# FRDM-MCXA153__Shield_Template.net
KiCad netlist of a schematic drawn in Altium Designer
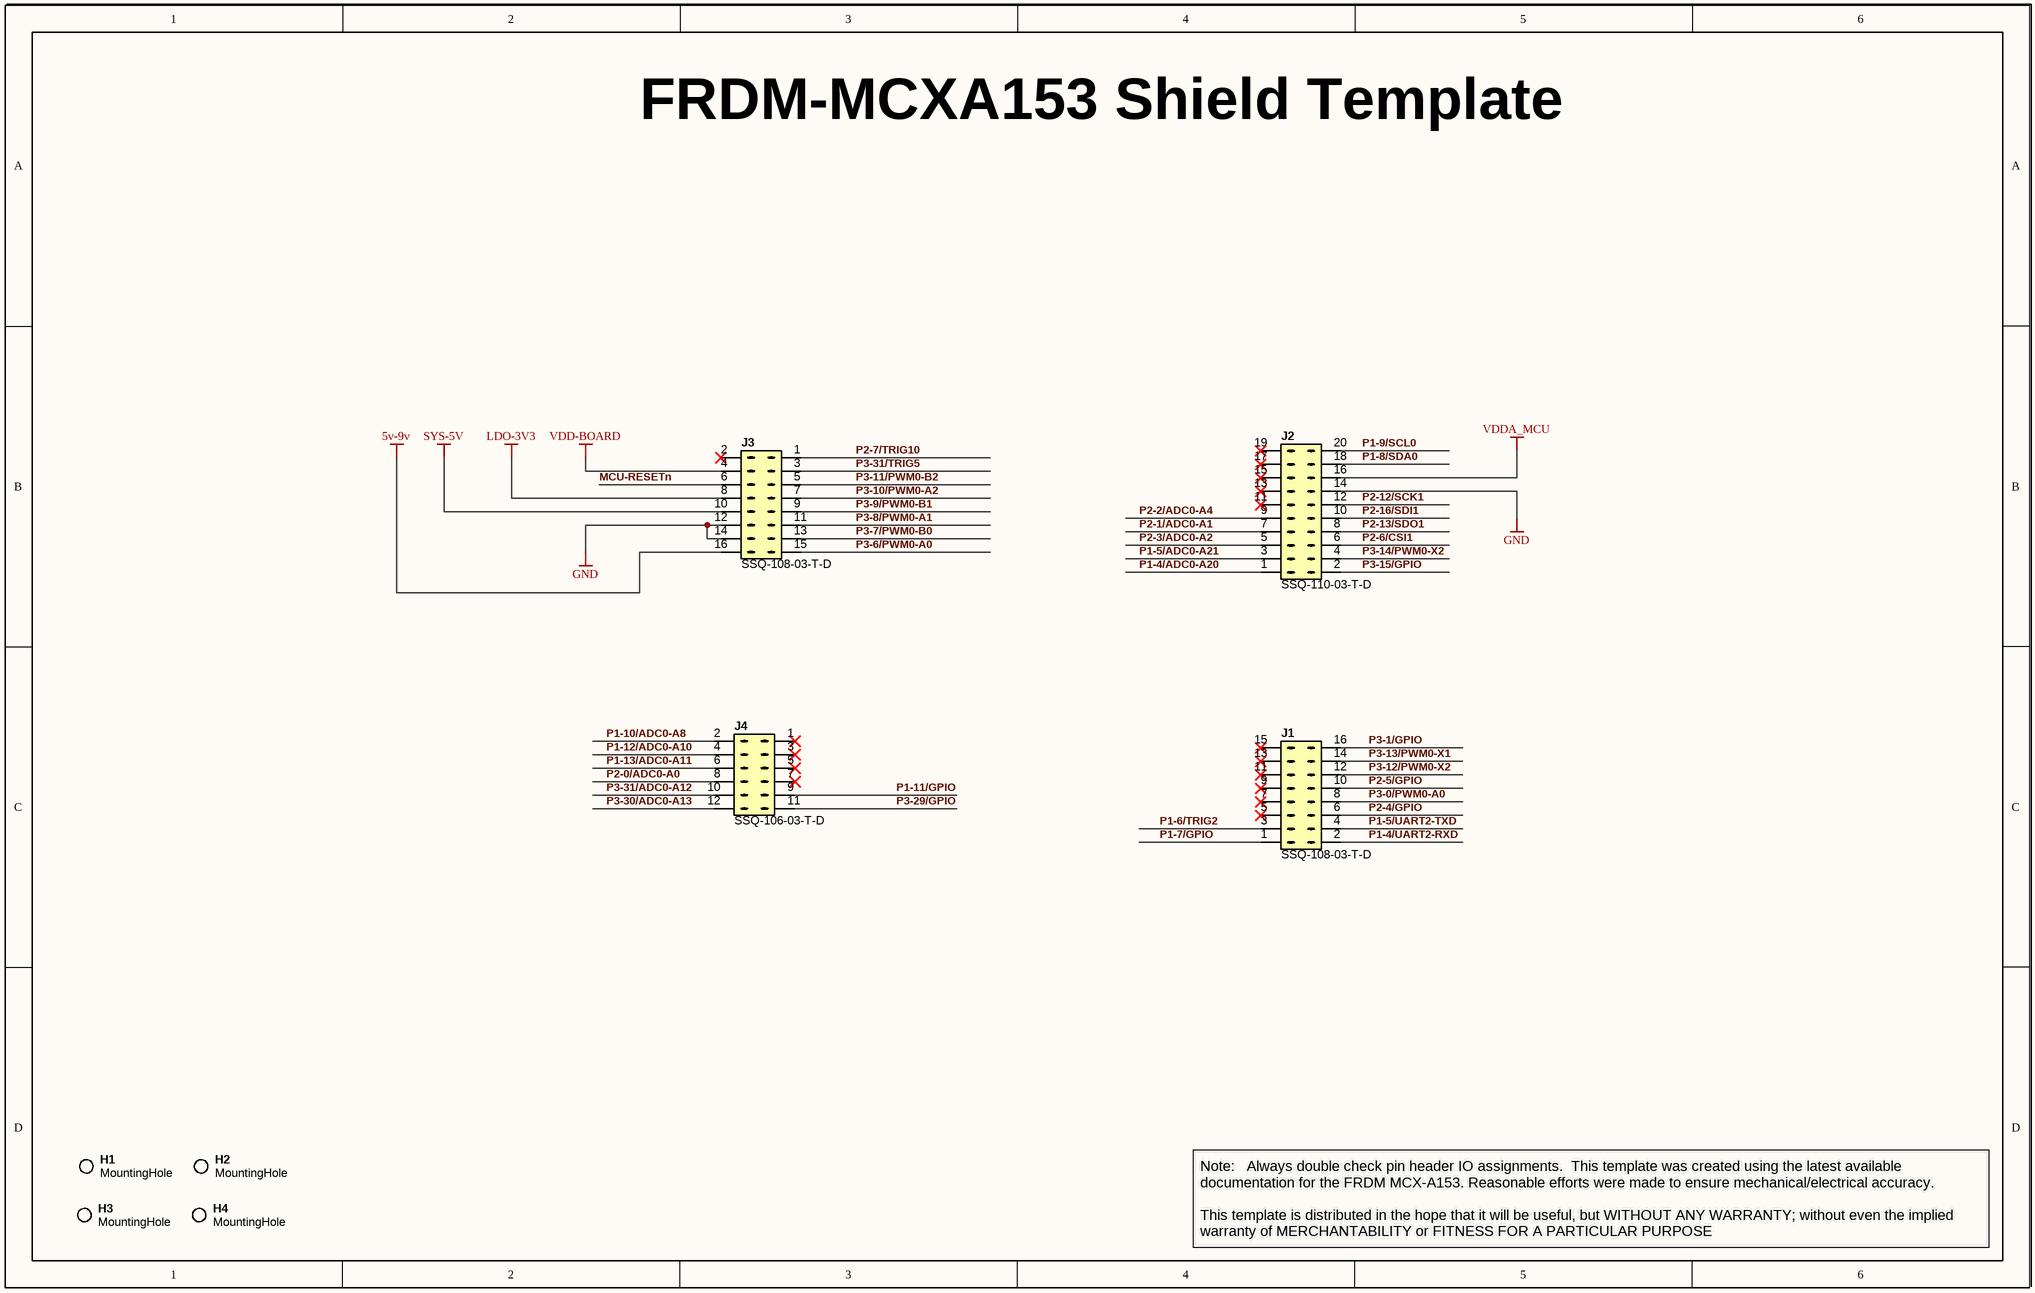
[diagram p0: FRDM-MCXA153__Shield_Template.SchDoc]

(export (version "E")
  (design (tool "Eeschema 10.0.6"))
  (components
    (comp (ref "H1")
      (value "MountingHole")
      (footprint "MountingHole_3.2mm_M3")
      (fields (field (name "Comment") "Mechanical_MountingHole"))
      (libsource (lib "altium-import") (part "root_0_Mechanical_MountingHole_"))
    )
    (comp (ref "H2")
      (value "MountingHole")
      (footprint "MountingHole_3.2mm_M3")
      (fields (field (name "Comment") "Mechanical_MountingHole"))
      (libsource (lib "altium-import") (part "root_0_Mechanical_MountingHole_"))
    )
    (comp (ref "H3")
      (value "MountingHole")
      (footprint "MountingHole_3.2mm_M3")
      (fields (field (name "Comment") "Mechanical_MountingHole"))
      (libsource (lib "altium-import") (part "root_0_Mechanical_MountingHole_"))
    )
    (comp (ref "H4")
      (value "MountingHole")
      (footprint "MountingHole_3.2mm_M3")
      (fields (field (name "Comment") "Mechanical_MountingHole"))
      (libsource (lib "altium-import") (part "root_0_Mechanical_MountingHole_"))
    )
    (comp (ref "J1")
      (value "SSQ-108-03-T-D")
      (footprint "SSQ-108-03-T-D")
      (fields (field (name "MANUFACTURER") "Samtec Inc."))
      (libsource (lib "FRDM-MCXA153__Shield__Template") (part "SSQ-108-03-T-D"))
    )
    (comp (ref "J2")
      (value "SSQ-110-03-T-D")
      (footprint "SSQ-110-03-T-D")
      (fields (field (name "MANUFACTURER") "Samtec Inc."))
      (libsource (lib "FRDM-MCXA153__Shield__Template") (part "SSQ-110-03-T-D"))
    )
    (comp (ref "J3")
      (value "SSQ-108-03-T-D")
      (footprint "SSQ-108-03-T-D")
      (fields (field (name "MANUFACTURER") "Samtec Inc."))
      (libsource (lib "") (part "SSQ-108-03-T-D_1"))
    )
    (comp (ref "J4")
      (value "SSQ-106-03-T-D")
      (footprint "SSQ-106-03-T-D")
      (fields (field (name "MANUFACTURER") "Samtec Inc."))
      (libsource (lib "FRDM-MCXA153__Shield__Template") (part "SSQ-106-03-T-D"))
    )
  )
  (nets
    (net (code "1") (name "/MCU-RESETn") (class "Default")
      (node (ref "J3") (pin "6") (pinfunction "Pin_6_6") (pintype "passive"))
    )
    (net (code "2") (name "/P1-4{slash}ADC0-A20") (class "Default")
      (node (ref "J2") (pin "1") (pinfunction "Pin_1_1") (pintype "passive"))
    )
    (net (code "3") (name "/P1-4{slash}UART2-RXD") (class "Default")
      (node (ref "J1") (pin "2") (pinfunction "Pin_2_2") (pintype "passive"))
    )
    (net (code "4") (name "/P1-5{slash}ADC0-A21") (class "Default")
      (node (ref "J2") (pin "3") (pinfunction "Pin_3_3") (pintype "passive"))
    )
    (net (code "5") (name "/P1-5{slash}UART2-TXD") (class "Default")
      (node (ref "J1") (pin "4") (pinfunction "Pin_4_4") (pintype "passive"))
    )
    (net (code "6") (name "/P1-6{slash}TRIG2") (class "Default")
      (node (ref "J1") (pin "3") (pinfunction "Pin_3_3") (pintype "passive"))
    )
    (net (code "7") (name "/P1-7{slash}GPIO") (class "Default")
      (node (ref "J1") (pin "1") (pinfunction "Pin_1_1") (pintype "passive"))
    )
    (net (code "8") (name "/P1-8{slash}SDA0") (class "Default")
      (node (ref "J2") (pin "18") (pinfunction "Pin_18_18") (pintype "passive"))
    )
    (net (code "9") (name "/P1-9{slash}SCL0") (class "Default")
      (node (ref "J2") (pin "20") (pinfunction "Pin_20_20") (pintype "passive"))
    )
    (net (code "10") (name "/P1-10{slash}ADC0-A8") (class "Default")
      (node (ref "J4") (pin "2") (pinfunction "Pin_2_2") (pintype "passive"))
    )
    (net (code "11") (name "/P1-11{slash}GPIO") (class "Default")
      (node (ref "J4") (pin "9") (pinfunction "Pin_9_9") (pintype "passive"))
    )
    (net (code "12") (name "/P1-12{slash}ADC0-A10") (class "Default")
      (node (ref "J4") (pin "4") (pinfunction "Pin_4_4") (pintype "passive"))
    )
    (net (code "13") (name "/P1-13{slash}ADC0-A11") (class "Default")
      (node (ref "J4") (pin "6") (pinfunction "Pin_6_6") (pintype "passive"))
    )
    (net (code "14") (name "/P2-0{slash}ADC0-A0") (class "Default")
      (node (ref "J4") (pin "8") (pinfunction "Pin_8_8") (pintype "passive"))
    )
    (net (code "15") (name "/P2-1{slash}ADC0-A1") (class "Default")
      (node (ref "J2") (pin "7") (pinfunction "Pin_7_7") (pintype "passive"))
    )
    (net (code "16") (name "/P2-2{slash}ADC0-A4") (class "Default")
      (node (ref "J2") (pin "9") (pinfunction "Pin_9_9") (pintype "passive"))
    )
    (net (code "17") (name "/P2-3{slash}ADC0-A2") (class "Default")
      (node (ref "J2") (pin "5") (pinfunction "Pin_5_5") (pintype "passive"))
    )
    (net (code "18") (name "/P2-4{slash}GPIO") (class "Default")
      (node (ref "J1") (pin "6") (pinfunction "Pin_6_6") (pintype "passive"))
    )
    (net (code "19") (name "/P2-5{slash}GPIO") (class "Default")
      (node (ref "J1") (pin "10") (pinfunction "Pin_10_10") (pintype "passive"))
    )
    (net (code "20") (name "/P2-6{slash}CSI1") (class "Default")
      (node (ref "J2") (pin "6") (pinfunction "Pin_6_6") (pintype "passive"))
    )
    (net (code "21") (name "/P2-7{slash}TRIG10") (class "Default")
      (node (ref "J3") (pin "1") (pinfunction "Pin_1_1") (pintype "passive"))
    )
    (net (code "22") (name "/P2-12{slash}SCK1") (class "Default")
      (node (ref "J2") (pin "12") (pinfunction "Pin_12_12") (pintype "passive"))
    )
    (net (code "23") (name "/P2-13{slash}SDO1") (class "Default")
      (node (ref "J2") (pin "8") (pinfunction "Pin_8_8") (pintype "passive"))
    )
    (net (code "24") (name "/P2-16{slash}SDI1") (class "Default")
      (node (ref "J2") (pin "10") (pinfunction "Pin_10_10") (pintype "passive"))
    )
    (net (code "25") (name "/P3-0{slash}PWM0-A0") (class "Default")
      (node (ref "J1") (pin "8") (pinfunction "Pin_8_8") (pintype "passive"))
    )
    (net (code "26") (name "/P3-1{slash}GPIO") (class "Default")
      (node (ref "J1") (pin "16") (pinfunction "Pin_16_16") (pintype "passive"))
    )
    (net (code "27") (name "/P3-6{slash}PWM0-A0") (class "Default")
      (node (ref "J3") (pin "15") (pinfunction "Pin_15_15") (pintype "passive"))
    )
    (net (code "28") (name "/P3-7{slash}PWM0-B0") (class "Default")
      (node (ref "J3") (pin "13") (pinfunction "Pin_13_13") (pintype "passive"))
    )
    (net (code "29") (name "/P3-8{slash}PWM0-A1") (class "Default")
      (node (ref "J3") (pin "11") (pinfunction "Pin_11_11") (pintype "passive"))
    )
    (net (code "30") (name "/P3-9{slash}PWM0-B1") (class "Default")
      (node (ref "J3") (pin "9") (pinfunction "Pin_9_9") (pintype "passive"))
    )
    (net (code "31") (name "/P3-10{slash}PWM0-A2") (class "Default")
      (node (ref "J3") (pin "7") (pinfunction "Pin_7_7") (pintype "passive"))
    )
    (net (code "32") (name "/P3-11{slash}PWM0-B2") (class "Default")
      (node (ref "J3") (pin "5") (pinfunction "Pin_5_5") (pintype "passive"))
    )
    (net (code "33") (name "/P3-12{slash}PWM0-X2") (class "Default")
      (node (ref "J1") (pin "12") (pinfunction "Pin_12_12") (pintype "passive"))
    )
    (net (code "34") (name "/P3-13{slash}PWM0-X1") (class "Default")
      (node (ref "J1") (pin "14") (pinfunction "Pin_14_14") (pintype "passive"))
    )
    (net (code "35") (name "/P3-14{slash}PWM0-X2") (class "Default")
      (node (ref "J2") (pin "4") (pinfunction "Pin_4_4") (pintype "passive"))
    )
    (net (code "36") (name "/P3-15{slash}GPIO") (class "Default")
      (node (ref "J2") (pin "2") (pinfunction "Pin_2_2") (pintype "passive"))
    )
    (net (code "37") (name "/P3-29{slash}GPIO") (class "Default")
      (node (ref "J4") (pin "11") (pinfunction "Pin_11_11") (pintype "passive"))
    )
    (net (code "38") (name "/P3-30{slash}ADC0-A13") (class "Default")
      (node (ref "J4") (pin "12") (pinfunction "Pin_12_12") (pintype "passive"))
    )
    (net (code "39") (name "/P3-31{slash}ADC0-A12") (class "Default")
      (node (ref "J4") (pin "10") (pinfunction "Pin_10_10") (pintype "passive"))
    )
    (net (code "40") (name "/P3-31{slash}TRIG5") (class "Default")
      (node (ref "J3") (pin "3") (pinfunction "Pin_3_3") (pintype "passive"))
    )
    (net (code "41") (name "5v-9v") (class "Default")
      (node (ref "J3") (pin "16") (pinfunction "Pin_16_16") (pintype "passive"))
    )
    (net (code "42") (name "GND") (class "Default")
      (node (ref "J2") (pin "14") (pinfunction "Pin_14_14") (pintype "passive"))
      (node (ref "J3") (pin "12") (pinfunction "Pin_12_12") (pintype "passive"))
      (node (ref "J3") (pin "14") (pinfunction "Pin_14_14") (pintype "passive"))
    )
    (net (code "43") (name "LDO-3V3") (class "Default")
      (node (ref "J3") (pin "8") (pinfunction "Pin_8_8") (pintype "passive"))
    )
    (net (code "44") (name "SYS-5V") (class "Default")
      (node (ref "J3") (pin "10") (pinfunction "Pin_10_10") (pintype "passive"))
    )
    (net (code "45") (name "VDD-BOARD") (class "Default")
      (node (ref "J3") (pin "4") (pinfunction "Pin_4_4") (pintype "passive"))
    )
    (net (code "46") (name "VDDA_MCU") (class "Default")
      (node (ref "J2") (pin "16") (pinfunction "Pin_16_16") (pintype "passive"))
    )
    (net (code "47") (name "unconnected-(J1-Pin_5-Pad5)") (class "Default")
      (node (ref "J1") (pin "5") (pinfunction "Pin_5_5") (pintype "passive+no_connect"))
    )
    (net (code "48") (name "unconnected-(J1-Pin_7-Pad7)") (class "Default")
      (node (ref "J1") (pin "7") (pinfunction "Pin_7_7") (pintype "passive+no_connect"))
    )
    (net (code "49") (name "unconnected-(J1-Pin_9-Pad9)") (class "Default")
      (node (ref "J1") (pin "9") (pinfunction "Pin_9_9") (pintype "passive+no_connect"))
    )
    (net (code "50") (name "unconnected-(J1-Pin_11-Pad11)") (class "Default")
      (node (ref "J1") (pin "11") (pinfunction "Pin_11_11") (pintype "passive+no_connect"))
    )
    (net (code "51") (name "unconnected-(J1-Pin_13-Pad13)") (class "Default")
      (node (ref "J1") (pin "13") (pinfunction "Pin_13_13") (pintype "passive+no_connect"))
    )
    (net (code "52") (name "unconnected-(J1-Pin_15-Pad15)") (class "Default")
      (node (ref "J1") (pin "15") (pinfunction "Pin_15_15") (pintype "passive+no_connect"))
    )
    (net (code "53") (name "unconnected-(J2-Pin_11-Pad11)") (class "Default")
      (node (ref "J2") (pin "11") (pinfunction "Pin_11_11") (pintype "passive+no_connect"))
    )
    (net (code "54") (name "unconnected-(J2-Pin_13-Pad13)") (class "Default")
      (node (ref "J2") (pin "13") (pinfunction "Pin_13_13") (pintype "passive+no_connect"))
    )
    (net (code "55") (name "unconnected-(J2-Pin_15-Pad15)") (class "Default")
      (node (ref "J2") (pin "15") (pinfunction "Pin_15_15") (pintype "passive+no_connect"))
    )
    (net (code "56") (name "unconnected-(J2-Pin_17-Pad17)") (class "Default")
      (node (ref "J2") (pin "17") (pinfunction "Pin_17_17") (pintype "passive+no_connect"))
    )
    (net (code "57") (name "unconnected-(J2-Pin_19-Pad19)") (class "Default")
      (node (ref "J2") (pin "19") (pinfunction "Pin_19_19") (pintype "passive+no_connect"))
    )
    (net (code "58") (name "unconnected-(J3-Pin_2-Pad2)") (class "Default")
      (node (ref "J3") (pin "2") (pinfunction "Pin_2_2") (pintype "passive+no_connect"))
    )
    (net (code "59") (name "unconnected-(J4-Pin_1-Pad1)") (class "Default")
      (node (ref "J4") (pin "1") (pinfunction "Pin_1_1") (pintype "passive+no_connect"))
    )
    (net (code "60") (name "unconnected-(J4-Pin_3-Pad3)") (class "Default")
      (node (ref "J4") (pin "3") (pinfunction "Pin_3_3") (pintype "passive+no_connect"))
    )
    (net (code "61") (name "unconnected-(J4-Pin_5-Pad5)") (class "Default")
      (node (ref "J4") (pin "5") (pinfunction "Pin_5_5") (pintype "passive+no_connect"))
    )
    (net (code "62") (name "unconnected-(J4-Pin_7-Pad7)") (class "Default")
      (node (ref "J4") (pin "7") (pinfunction "Pin_7_7") (pintype "passive+no_connect"))
    )
  )
)
